# M3020X.net
KiCad netlist of a schematic drawn in EAGLE
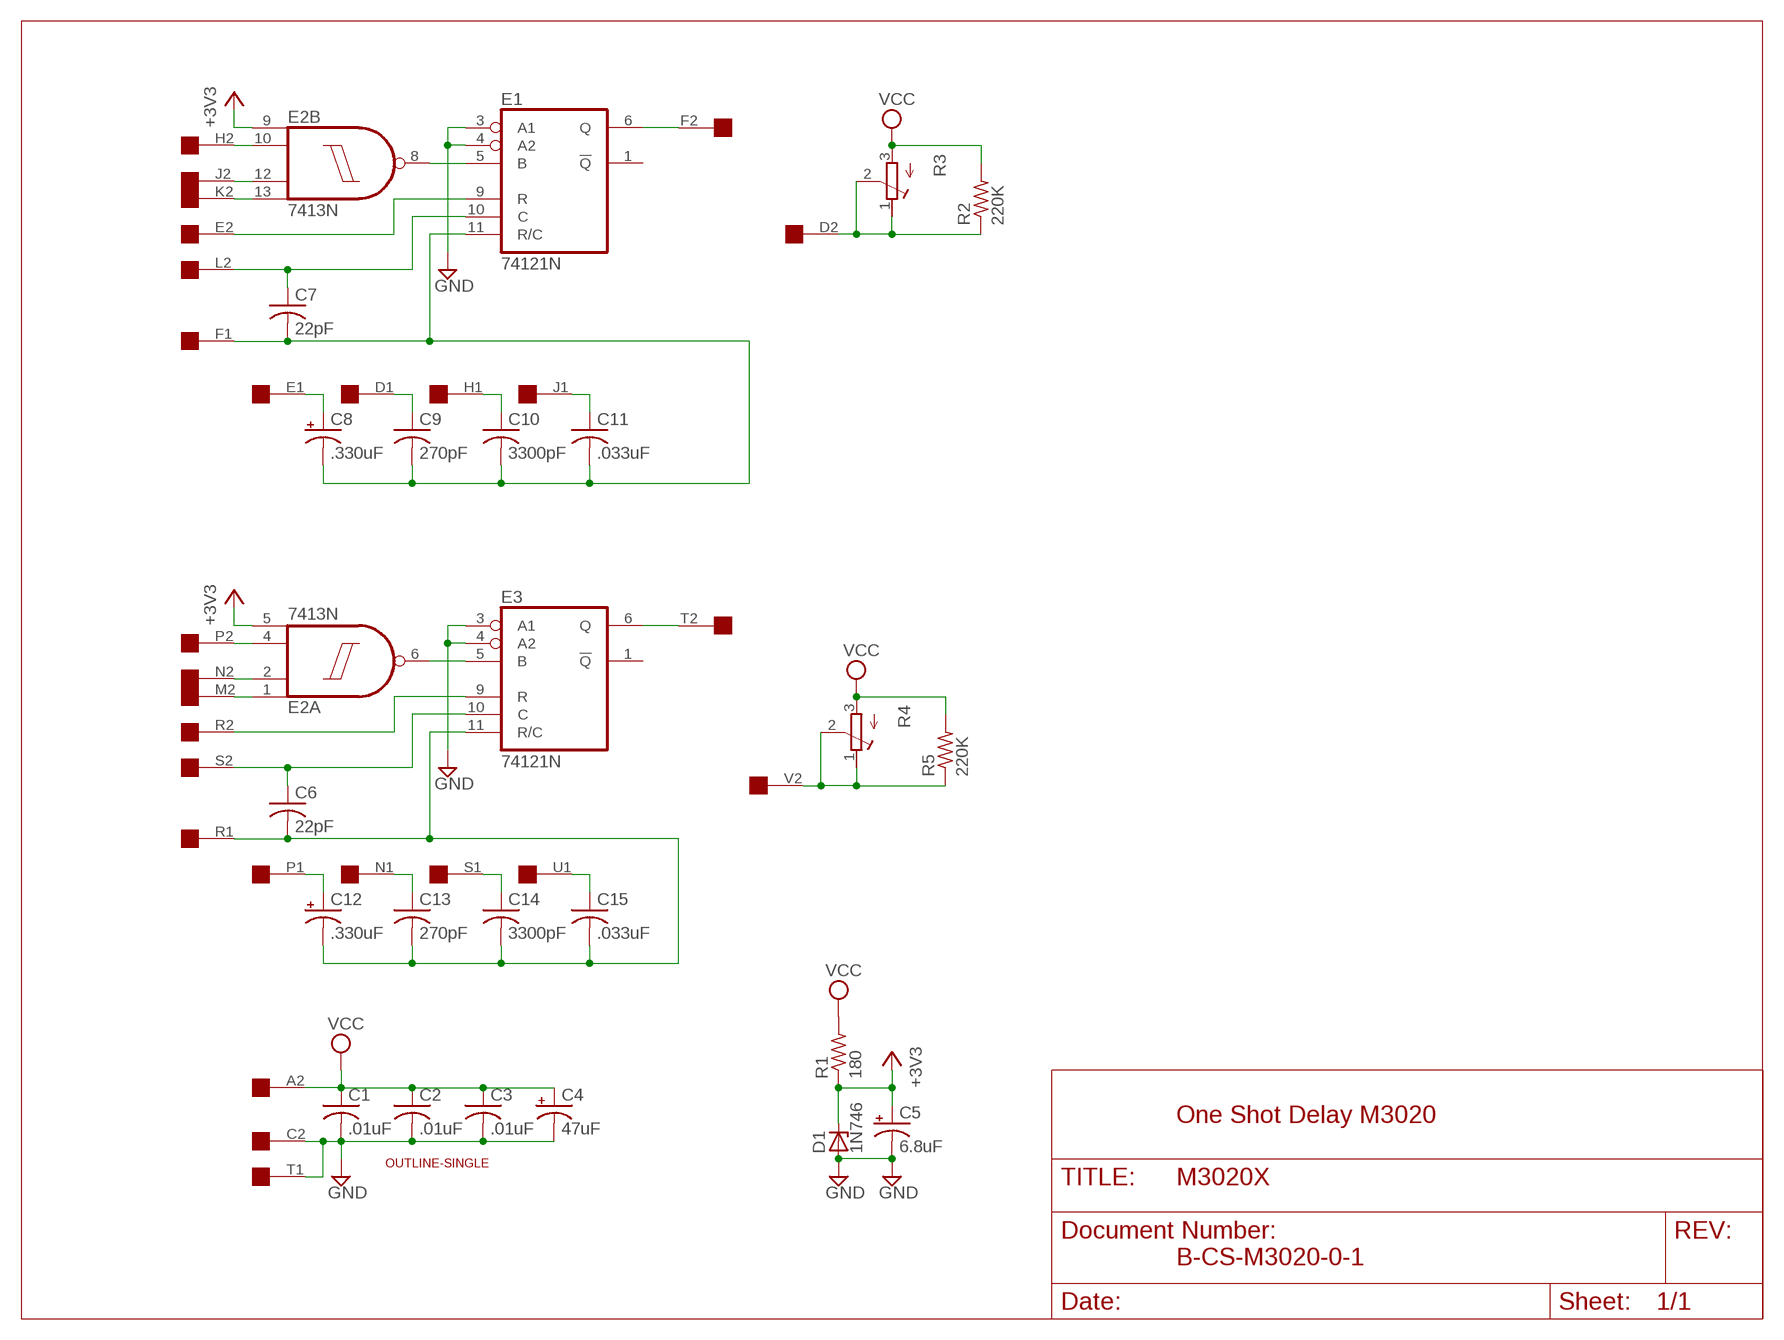
[diagram p0: schematic, sheet 1]

(export (version "E")
  (design (tool "Eeschema 10.0.6"))
  (components
    (comp (ref "C1")
      (value ".01uF")
      (footprint "eagle-import:C050-025X075")
      (libsource (lib "eagle-import") (part "C-US050-025X075"))
    )
    (comp (ref "C2")
      (value ".01uF")
      (footprint "eagle-import:C050-025X075")
      (libsource (lib "eagle-import") (part "C-US050-025X075"))
    )
    (comp (ref "C3")
      (value ".01uF")
      (footprint "eagle-import:C050-025X075")
      (libsource (lib "eagle-import") (part "C-US050-025X075"))
    )
    (comp (ref "C4")
      (value "47uF")
      (footprint "eagle-import:E12-8")
      (libsource (lib "eagle-import") (part "CPOL-USE20-8AXIAL"))
    )
    (comp (ref "C5")
      (value "6.8uF")
      (footprint "eagle-import:E12-8")
      (libsource (lib "eagle-import") (part "CPOL-USE20-8AXIAL"))
    )
    (comp (ref "C6")
      (value "22pF")
      (footprint "eagle-import:C050-025X075")
      (libsource (lib "eagle-import") (part "C-US050-025X075"))
    )
    (comp (ref "C7")
      (value "22pF")
      (footprint "eagle-import:C050-025X075")
      (libsource (lib "eagle-import") (part "C-US050-025X075"))
    )
    (comp (ref "C8")
      (value ".330uF")
      (footprint "eagle-import:E15-5")
      (libsource (lib "eagle-import") (part "CPOL-USE15-5AXIAL"))
    )
    (comp (ref "C9")
      (value "270pF")
      (footprint "eagle-import:C075-032X103")
      (libsource (lib "eagle-import") (part "C-US075-032X103"))
    )
    (comp (ref "C10")
      (value "3300pF")
      (footprint "eagle-import:C102-043X133")
      (libsource (lib "eagle-import") (part "C-US102-043X133"))
    )
    (comp (ref "C11")
      (value ".033uF")
      (footprint "eagle-import:C225-062X268")
      (libsource (lib "eagle-import") (part "C-US225-062X268"))
    )
    (comp (ref "C12")
      (value ".330uF")
      (footprint "eagle-import:E15-5")
      (libsource (lib "eagle-import") (part "CPOL-USE15-5AXIAL"))
    )
    (comp (ref "C13")
      (value "270pF")
      (footprint "eagle-import:C075-032X103")
      (libsource (lib "eagle-import") (part "C-US075-032X103"))
    )
    (comp (ref "C14")
      (value "3300pF")
      (footprint "eagle-import:C102-043X133")
      (libsource (lib "eagle-import") (part "C-US102-043X133"))
    )
    (comp (ref "C15")
      (value ".033uF")
      (footprint "eagle-import:C225-062X268")
      (libsource (lib "eagle-import") (part "C-US225-062X268"))
    )
    (comp (ref "D1")
      (value "1N746")
      (footprint "eagle-import:DO35Z10")
      (libsource (lib "eagle-import") (part "ZENER-DIODEDO35Z10"))
    )
    (comp (ref "E1")
      (value "74121N")
      (footprint "eagle-import:DIL14")
      (libsource (lib "eagle-import") (part "74121N"))
    )
    (comp (ref "E2")
      (value "7413N")
      (footprint "eagle-import:DIL14")
      (libsource (lib "eagle-import") (part "7413N"))
    )
    (comp (ref "E3")
      (value "74121N")
      (footprint "eagle-import:DIL14")
      (libsource (lib "eagle-import") (part "74121N"))
    )
    (comp (ref "R1")
      (value "180")
      (footprint "eagle-import:0207_10")
      (libsource (lib "eagle-import") (part "R-US_0207/10"))
    )
    (comp (ref "R2")
      (value "220K")
      (footprint "eagle-import:0207_10")
      (libsource (lib "eagle-import") (part "R-US_0207/10"))
    )
    (comp (ref "R3")
      (value "275P")
      (footprint "eagle-import:3006Y")
      (libsource (lib "eagle-import") (part "275P"))
    )
    (comp (ref "R4")
      (value "275P")
      (footprint "eagle-import:3006Y")
      (libsource (lib "eagle-import") (part "275P"))
    )
    (comp (ref "R5")
      (value "220K")
      (footprint "eagle-import:0207_10")
      (libsource (lib "eagle-import") (part "R-US_0207/10"))
    )
    (comp (ref "U$1")
      (value "OUTLINE-SINGLE")
      (footprint "eagle-import:SINGLE")
      (libsource (lib "eagle-import") (part "OUTLINE-SINGLE"))
    )
    (comp (ref "U$2")
      (value "SINGLE")
      (footprint "eagle-import:EDGE-CON2")
      (libsource (lib "eagle-import") (part "SINGLE"))
    )
  )
  (nets
    (net (code "1") (name "+3V3") (class "Default")
      (node (ref "C5") (pin "+") (pinfunction "+_+") (pintype "passive"))
      (node (ref "D1") (pin "C") (pinfunction "C_C") (pintype "passive"))
      (node (ref "E2") (pin "5") (pinfunction "I3_5") (pintype "input"))
      (node (ref "E2") (pin "9") (pinfunction "I0_9") (pintype "input"))
      (node (ref "R1") (pin "1") (pinfunction "1_1") (pintype "passive"))
    )
    (net (code "2") (name "GND") (class "Default")
      (node (ref "C1") (pin "2") (pinfunction "2_2") (pintype "passive"))
      (node (ref "C2") (pin "2") (pinfunction "2_2") (pintype "passive"))
      (node (ref "C3") (pin "2") (pinfunction "2_2") (pintype "passive"))
      (node (ref "C4") (pin "-") (pinfunction "-_-") (pintype "passive"))
      (node (ref "C5") (pin "-") (pinfunction "-_-") (pintype "passive"))
      (node (ref "D1") (pin "A") (pinfunction "A_A") (pintype "passive"))
      (node (ref "E1") (pin "3") (pinfunction "A1_3") (pintype "input"))
      (node (ref "E1") (pin "4") (pinfunction "A2_4") (pintype "input"))
      (node (ref "E3") (pin "3") (pinfunction "A1_3") (pintype "input"))
      (node (ref "E3") (pin "4") (pinfunction "A2_4") (pintype "input"))
      (node (ref "U$2") (pin "C2") (pinfunction "1_C2") (pintype "bidirectional"))
      (node (ref "U$2") (pin "T1") (pinfunction "1_T1") (pintype "bidirectional"))
    )
    (net (code "3") (name "Net-(E1A-B)") (class "Default")
      (node (ref "E1") (pin "5") (pinfunction "B_5") (pintype "input"))
      (node (ref "E2") (pin "8") (pinfunction "O_8") (pintype "output"))
    )
    (net (code "4") (name "Net-(E1A-C)") (class "Default")
      (node (ref "C7") (pin "1") (pinfunction "1_1") (pintype "passive"))
      (node (ref "E1") (pin "10") (pinfunction "C_10") (pintype "input"))
      (node (ref "U$2") (pin "L2") (pinfunction "1_L2") (pintype "bidirectional"))
    )
    (net (code "5") (name "Net-(E1A-Q)") (class "Default")
      (node (ref "E1") (pin "6") (pinfunction "Q_6") (pintype "output"))
      (node (ref "U$2") (pin "F2") (pinfunction "1_F2") (pintype "bidirectional"))
    )
    (net (code "6") (name "Net-(E1A-R)") (class "Default")
      (node (ref "E1") (pin "9") (pinfunction "R_9") (pintype "input"))
      (node (ref "U$2") (pin "E2") (pinfunction "1_E2") (pintype "bidirectional"))
    )
    (net (code "7") (name "Net-(E1A-R{slash}C)") (class "Default")
      (node (ref "C10") (pin "2") (pinfunction "2_2") (pintype "passive"))
      (node (ref "C11") (pin "2") (pinfunction "2_2") (pintype "passive"))
      (node (ref "C7") (pin "2") (pinfunction "2_2") (pintype "passive"))
      (node (ref "C8") (pin "-") (pinfunction "-_-") (pintype "passive"))
      (node (ref "C9") (pin "2") (pinfunction "2_2") (pintype "passive"))
      (node (ref "E1") (pin "11") (pinfunction "R/C_11") (pintype "input"))
      (node (ref "U$2") (pin "F1") (pinfunction "1_F1") (pintype "bidirectional"))
    )
    (net (code "8") (name "Net-(E2A-I0)") (class "Default")
      (node (ref "E2") (pin "1") (pinfunction "I0_1") (pintype "input"))
      (node (ref "U$2") (pin "M2") (pinfunction "1_M2") (pintype "bidirectional"))
    )
    (net (code "9") (name "Net-(E2A-I1)") (class "Default")
      (node (ref "E2") (pin "2") (pinfunction "I1_2") (pintype "input"))
      (node (ref "U$2") (pin "N2") (pinfunction "1_N2") (pintype "bidirectional"))
    )
    (net (code "10") (name "Net-(E2A-I2)") (class "Default")
      (node (ref "E2") (pin "4") (pinfunction "I2_4") (pintype "input"))
      (node (ref "U$2") (pin "P2") (pinfunction "1_P2") (pintype "bidirectional"))
    )
    (net (code "11") (name "Net-(E2A-O)") (class "Default")
      (node (ref "E2") (pin "6") (pinfunction "O_6") (pintype "output"))
      (node (ref "E3") (pin "5") (pinfunction "B_5") (pintype "input"))
    )
    (net (code "12") (name "Net-(E2B-I1)") (class "Default")
      (node (ref "E2") (pin "10") (pinfunction "I1_10") (pintype "input"))
      (node (ref "U$2") (pin "H2") (pinfunction "1_H2") (pintype "bidirectional"))
    )
    (net (code "13") (name "Net-(E2B-I2)") (class "Default")
      (node (ref "E2") (pin "12") (pinfunction "I2_12") (pintype "input"))
      (node (ref "U$2") (pin "J2") (pinfunction "1_J2") (pintype "bidirectional"))
    )
    (net (code "14") (name "Net-(E2B-I3)") (class "Default")
      (node (ref "E2") (pin "13") (pinfunction "I3_13") (pintype "input"))
      (node (ref "U$2") (pin "K2") (pinfunction "1_K2") (pintype "bidirectional"))
    )
    (net (code "15") (name "Net-(E3A-C)") (class "Default")
      (node (ref "C6") (pin "1") (pinfunction "1_1") (pintype "passive"))
      (node (ref "E3") (pin "10") (pinfunction "C_10") (pintype "input"))
      (node (ref "U$2") (pin "S2") (pinfunction "1_S2") (pintype "bidirectional"))
    )
    (net (code "16") (name "Net-(E3A-Q)") (class "Default")
      (node (ref "E3") (pin "6") (pinfunction "Q_6") (pintype "output"))
      (node (ref "U$2") (pin "T2") (pinfunction "1_T2") (pintype "bidirectional"))
    )
    (net (code "17") (name "Net-(E3A-R)") (class "Default")
      (node (ref "E3") (pin "9") (pinfunction "R_9") (pintype "input"))
      (node (ref "U$2") (pin "R2") (pinfunction "1_R2") (pintype "bidirectional"))
    )
    (net (code "18") (name "Net-(E3A-R{slash}C)") (class "Default")
      (node (ref "C12") (pin "-") (pinfunction "-_-") (pintype "passive"))
      (node (ref "C13") (pin "2") (pinfunction "2_2") (pintype "passive"))
      (node (ref "C14") (pin "2") (pinfunction "2_2") (pintype "passive"))
      (node (ref "C15") (pin "2") (pinfunction "2_2") (pintype "passive"))
      (node (ref "C6") (pin "2") (pinfunction "2_2") (pintype "passive"))
      (node (ref "E3") (pin "11") (pinfunction "R/C_11") (pintype "input"))
      (node (ref "U$2") (pin "R1") (pinfunction "1_R1") (pintype "bidirectional"))
    )
    (net (code "19") (name "Net-(R3-A)") (class "Default")
      (node (ref "R2") (pin "1") (pinfunction "1_1") (pintype "passive"))
      (node (ref "R3") (pin "1") (pinfunction "A_1") (pintype "passive"))
      (node (ref "R3") (pin "2") (pinfunction "S_2") (pintype "passive"))
      (node (ref "U$2") (pin "D2") (pinfunction "1_D2") (pintype "bidirectional"))
    )
    (net (code "20") (name "Net-(R4-A)") (class "Default")
      (node (ref "R4") (pin "1") (pinfunction "A_1") (pintype "passive"))
      (node (ref "R4") (pin "2") (pinfunction "S_2") (pintype "passive"))
      (node (ref "R5") (pin "1") (pinfunction "1_1") (pintype "passive"))
      (node (ref "U$2") (pin "V2") (pinfunction "1_V2") (pintype "bidirectional"))
    )
    (net (code "21") (name "Net-(U$2AC-1)") (class "Default")
      (node (ref "C14") (pin "1") (pinfunction "1_1") (pintype "passive"))
      (node (ref "U$2") (pin "S1") (pinfunction "1_S1") (pintype "bidirectional"))
    )
    (net (code "22") (name "Net-(U$2AG-1)") (class "Default")
      (node (ref "C15") (pin "1") (pinfunction "1_1") (pintype "passive"))
      (node (ref "U$2") (pin "U1") (pinfunction "1_U1") (pintype "bidirectional"))
    )
    (net (code "23") (name "Net-(U$2G-1)") (class "Default")
      (node (ref "C9") (pin "1") (pinfunction "1_1") (pintype "passive"))
      (node (ref "U$2") (pin "D1") (pinfunction "1_D1") (pintype "bidirectional"))
    )
    (net (code "24") (name "Net-(U$2I-1)") (class "Default")
      (node (ref "C8") (pin "+") (pinfunction "+_+") (pintype "passive"))
      (node (ref "U$2") (pin "E1") (pinfunction "1_E1") (pintype "bidirectional"))
    )
    (net (code "25") (name "Net-(U$2M-1)") (class "Default")
      (node (ref "C10") (pin "1") (pinfunction "1_1") (pintype "passive"))
      (node (ref "U$2") (pin "H1") (pinfunction "1_H1") (pintype "bidirectional"))
    )
    (net (code "26") (name "Net-(U$2O-1)") (class "Default")
      (node (ref "C11") (pin "1") (pinfunction "1_1") (pintype "passive"))
      (node (ref "U$2") (pin "J1") (pinfunction "1_J1") (pintype "bidirectional"))
    )
    (net (code "27") (name "Net-(U$2W-1)") (class "Default")
      (node (ref "C13") (pin "1") (pinfunction "1_1") (pintype "passive"))
      (node (ref "U$2") (pin "N1") (pinfunction "1_N1") (pintype "bidirectional"))
    )
    (net (code "28") (name "Net-(U$2Y-1)") (class "Default")
      (node (ref "C12") (pin "+") (pinfunction "+_+") (pintype "passive"))
      (node (ref "U$2") (pin "P1") (pinfunction "1_P1") (pintype "bidirectional"))
    )
    (net (code "29") (name "VCC") (class "Default")
      (node (ref "C1") (pin "1") (pinfunction "1_1") (pintype "passive"))
      (node (ref "C2") (pin "1") (pinfunction "1_1") (pintype "passive"))
      (node (ref "C3") (pin "1") (pinfunction "1_1") (pintype "passive"))
      (node (ref "C4") (pin "+") (pinfunction "+_+") (pintype "passive"))
      (node (ref "R1") (pin "2") (pinfunction "2_2") (pintype "passive"))
      (node (ref "R2") (pin "2") (pinfunction "2_2") (pintype "passive"))
      (node (ref "R3") (pin "3") (pinfunction "E_3") (pintype "passive"))
      (node (ref "R4") (pin "3") (pinfunction "E_3") (pintype "passive"))
      (node (ref "R5") (pin "2") (pinfunction "2_2") (pintype "passive"))
      (node (ref "U$2") (pin "A2") (pinfunction "1_A2") (pintype "bidirectional"))
    )
    (net (code "30") (name "unconnected-(E1A-~{Q}-Pad1)") (class "Default")
      (node (ref "E1") (pin "1") (pinfunction "~{Q}_1") (pintype "output"))
    )
    (net (code "31") (name "unconnected-(E3A-~{Q}-Pad1)") (class "Default")
      (node (ref "E3") (pin "1") (pinfunction "~{Q}_1") (pintype "output"))
    )
  )
)
